# PSM_footprint.net
KiCad netlist of a schematic drawn in Altium Designer
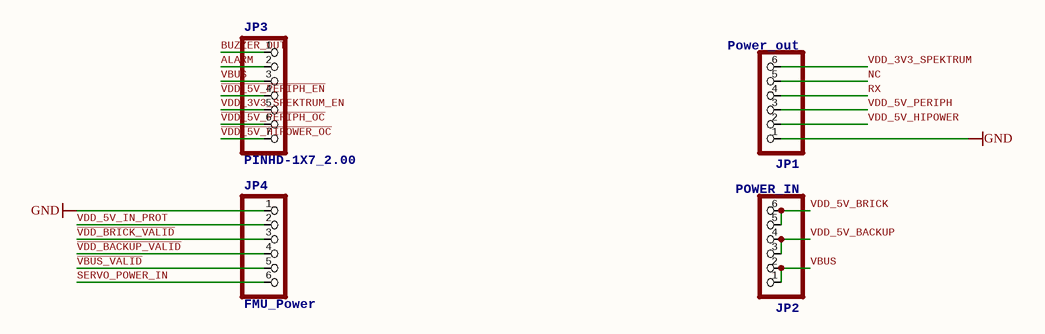
[diagram p0: PSM_footprint.SchDoc]

(export (version "E")
  (design (tool "Eeschema 10.0.6"))
  (components
    (comp (ref "JP1")
      (value "Power_out")
      (footprint "PSM:1X06M")
      (libsource (lib "altium-import") (part "root_2_PINHD-1X6_2.00_"))
    )
    (comp (ref "JP2")
      (value "POWER_IN")
      (footprint "PSM:1X06M")
      (libsource (lib "altium-import") (part "root_2_PINHD-1X6_2.00_"))
    )
    (comp (ref "JP3")
      (value "PINHD-1X7_2.00")
      (footprint "PSM:1X07M")
      (libsource (lib "altium-import") (part "root_0_PINHD-1X7_2.00_"))
    )
    (comp (ref "JP4")
      (value "FMU_Power")
      (footprint "PSM:1X06M")
      (libsource (lib "altium-import") (part "root_0_PINHD-1X6_2.00_"))
    )
  )
  (nets
    (net (code "1") (name "/ALARM") (class "Default")
      (node (ref "JP3") (pin "2") (pinfunction "2_2") (pintype "passive"))
    )
    (net (code "2") (name "/BUZZER_OUT") (class "Default")
      (node (ref "JP3") (pin "1") (pinfunction "1_1") (pintype "passive"))
    )
    (net (code "3") (name "/NC") (class "Default")
      (node (ref "JP1") (pin "5") (pinfunction "5_5") (pintype "passive"))
    )
    (net (code "4") (name "/RX") (class "Default")
      (node (ref "JP1") (pin "4") (pinfunction "4_4") (pintype "passive"))
    )
    (net (code "5") (name "/SERVO_POWER_IN") (class "Default")
      (node (ref "JP4") (pin "6") (pinfunction "6_6") (pintype "passive"))
    )
    (net (code "6") (name "/VBUS") (class "Default")
      (node (ref "JP2") (pin "1") (pinfunction "1_1") (pintype "passive"))
      (node (ref "JP2") (pin "2") (pinfunction "2_2") (pintype "passive"))
      (node (ref "JP3") (pin "3") (pinfunction "3_3") (pintype "passive"))
    )
    (net (code "7") (name "/VDD_3V3_SPEKTRUM") (class "Default")
      (node (ref "JP1") (pin "6") (pinfunction "6_6") (pintype "passive"))
    )
    (net (code "8") (name "/VDD_3V3_SPEKTRUM_EN") (class "Default")
      (node (ref "JP3") (pin "5") (pinfunction "5_5") (pintype "passive"))
    )
    (net (code "9") (name "/VDD_5V_BACKUP") (class "Default")
      (node (ref "JP2") (pin "3") (pinfunction "3_3") (pintype "passive"))
      (node (ref "JP2") (pin "4") (pinfunction "4_4") (pintype "passive"))
    )
    (net (code "10") (name "/VDD_5V_BRICK") (class "Default")
      (node (ref "JP2") (pin "5") (pinfunction "5_5") (pintype "passive"))
      (node (ref "JP2") (pin "6") (pinfunction "6_6") (pintype "passive"))
    )
    (net (code "11") (name "/VDD_5V_HIPOWER") (class "Default")
      (node (ref "JP1") (pin "2") (pinfunction "2_2") (pintype "passive"))
    )
    (net (code "12") (name "/VDD_5V_IN_PROT") (class "Default")
      (node (ref "JP4") (pin "2") (pinfunction "2_2") (pintype "passive"))
    )
    (net (code "13") (name "/VDD_5V_PERIPH") (class "Default")
      (node (ref "JP1") (pin "3") (pinfunction "3_3") (pintype "passive"))
    )
    (net (code "14") (name "/~{VBUS_VALID}") (class "Default")
      (node (ref "JP4") (pin "5") (pinfunction "5_5") (pintype "passive"))
    )
    (net (code "15") (name "/~{VDD_5V_HIPOWER_OC}") (class "Default")
      (node (ref "JP3") (pin "7") (pinfunction "7_7") (pintype "passive"))
    )
    (net (code "16") (name "/~{VDD_5V_PERIPH_EN}") (class "Default")
      (node (ref "JP3") (pin "4") (pinfunction "4_4") (pintype "passive"))
    )
    (net (code "17") (name "/~{VDD_5V_PERIPH_OC}") (class "Default")
      (node (ref "JP3") (pin "6") (pinfunction "6_6") (pintype "passive"))
    )
    (net (code "18") (name "/~{VDD_BACKUP_VALID}") (class "Default")
      (node (ref "JP4") (pin "4") (pinfunction "4_4") (pintype "passive"))
    )
    (net (code "19") (name "/~{VDD_BRICK_VALID}") (class "Default")
      (node (ref "JP4") (pin "3") (pinfunction "3_3") (pintype "passive"))
    )
    (net (code "20") (name "GND") (class "Default")
      (node (ref "JP1") (pin "1") (pinfunction "1_1") (pintype "passive"))
      (node (ref "JP4") (pin "1") (pinfunction "1_1") (pintype "passive"))
    )
  )
)
